# 4_SDCard.net
KiCad netlist of a schematic drawn in Altium Designer
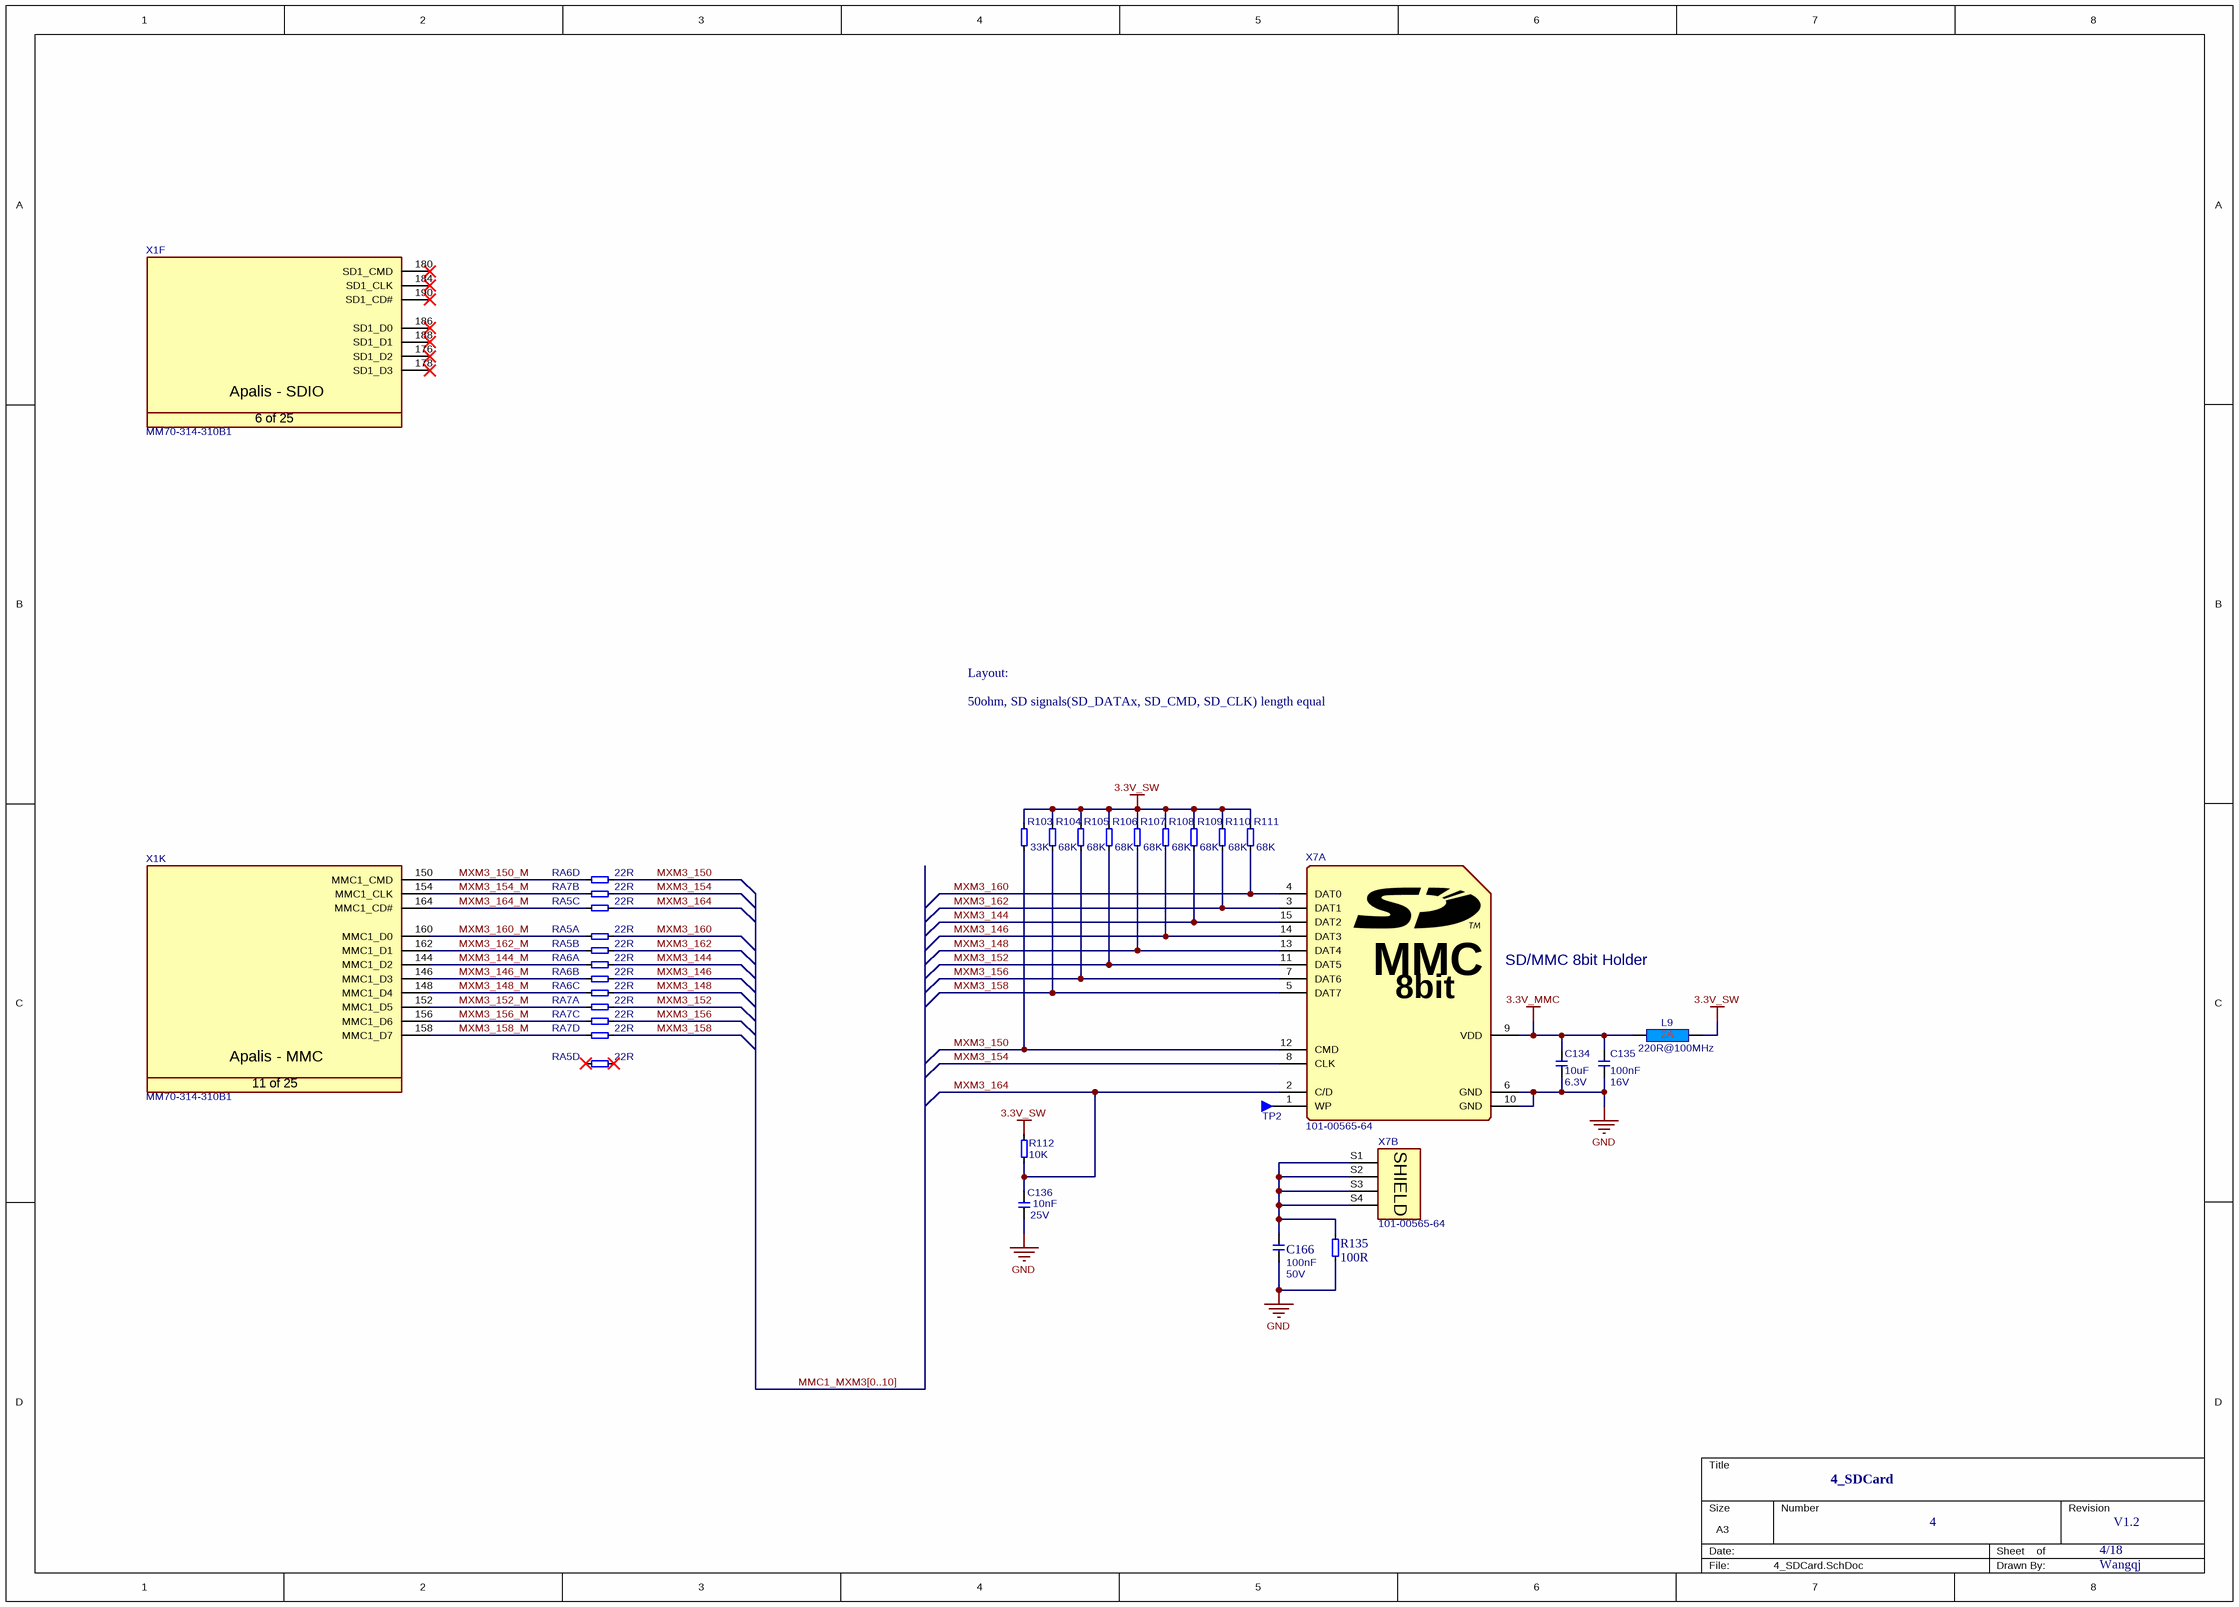
[diagram p0: 4_SDCard.SchDoc]

(export (version "E")
  (design (tool "Eeschema 10.0.6"))
  (components
    (comp (ref "C134")
      (value "10uF")
      (footprint "T_CAPC0603X33N")
      (description "Capacitor Ceramic X5R 10uF 6.3V 20% 0603")
      (fields (field (name "TOLERANCE") "20%") (field (name "RATING") "6.3V"))
      (libsource (lib "Apalis Evaluation Board") (part "C-X5R-10uF-6.3V-20%-0603"))
    )
    (comp (ref "C135")
      (value "100nF")
      (footprint "T_CAPC0603X33N")
      (description "Capacitor Ceramic X7R 100nF 16V 10% 0603")
      (fields (field (name "TOLERANCE") "10%") (field (name "RATING") "16V"))
      (libsource (lib "Apalis Evaluation Board") (part "C-X7R-100nF-16V-10%-0603"))
    )
    (comp (ref "C136")
      (value "10nF")
      (footprint "T_CAPC0603X33N")
      (description "Capacitor Ceramic X7R 10nF 25V 10% 0603")
      (fields (field (name "TOLERANCE") "10%") (field (name "RATING") "25V"))
      (libsource (lib "Apalis Evaluation Board") (part "C-X7R-10nF-25V-10%-0603"))
    )
    (comp (ref "C166")
      (value "100nF")
      (footprint "T_CAPC0603X33N")
      (description "Capacitor Ceramic X7R 100nF 50V 20% 0603")
      (fields (field (name "TOLERANCE") "20%") (field (name "RATING") "50V"))
      (libsource (lib "Apalis Evaluation Board") (part "C-100nF-50V-20%-0603-X7R"))
    )
    (comp (ref "L9")
      (value "220R@100MHz")
      (footprint "INDC1608X95N")
      (description "220R@100MHz 2A EMI FILTER")
      (fields (field (name "TOLERANCE") "25%"))
      (libsource (lib "Apalis Evaluation Board") (part "L-220R@100MHz-2A-25%-0603"))
    )
    (comp (ref "R103")
      (value "33K")
      (footprint "T_RESC0603X30N")
      (description "Resistor 33 Kohm 63mW 5% 0603")
      (fields (field (name "TOLERANCE") "5%"))
      (libsource (lib "Apalis Evaluation Board") (part "R-33KR-63mW-5%-0603"))
    )
    (comp (ref "R104")
      (value "68K")
      (footprint "T_RESC0603X30N")
      (description "Resistor 68 Kohm 63mW 5% 0603")
      (fields (field (name "TOLERANCE") "5%"))
      (libsource (lib "Apalis Evaluation Board") (part "R-68KR-63mW-5%-0603"))
    )
    (comp (ref "R105")
      (value "68K")
      (footprint "T_RESC0603X30N")
      (description "Resistor 68 Kohm 63mW 5% 0603")
      (fields (field (name "TOLERANCE") "5%"))
      (libsource (lib "Apalis Evaluation Board") (part "R-68KR-63mW-5%-0603"))
    )
    (comp (ref "R106")
      (value "68K")
      (footprint "T_RESC0603X30N")
      (description "Resistor 68 Kohm 63mW 5% 0603")
      (fields (field (name "TOLERANCE") "5%"))
      (libsource (lib "Apalis Evaluation Board") (part "R-68KR-63mW-5%-0603"))
    )
    (comp (ref "R107")
      (value "68K")
      (footprint "T_RESC0603X30N")
      (description "Resistor 68 Kohm 63mW 5% 0603")
      (fields (field (name "TOLERANCE") "5%"))
      (libsource (lib "Apalis Evaluation Board") (part "R-68KR-63mW-5%-0603"))
    )
    (comp (ref "R108")
      (value "68K")
      (footprint "T_RESC0603X30N")
      (description "Resistor 68 Kohm 63mW 5% 0603")
      (fields (field (name "TOLERANCE") "5%"))
      (libsource (lib "Apalis Evaluation Board") (part "R-68KR-63mW-5%-0603"))
    )
    (comp (ref "R109")
      (value "68K")
      (footprint "T_RESC0603X30N")
      (description "Resistor 68 Kohm 63mW 5% 0603")
      (fields (field (name "TOLERANCE") "5%"))
      (libsource (lib "Apalis Evaluation Board") (part "R-68KR-63mW-5%-0603"))
    )
    (comp (ref "R110")
      (value "68K")
      (footprint "T_RESC0603X30N")
      (description "Resistor 68 Kohm 63mW 5% 0603")
      (fields (field (name "TOLERANCE") "5%"))
      (libsource (lib "Apalis Evaluation Board") (part "R-68KR-63mW-5%-0603"))
    )
    (comp (ref "R111")
      (value "68K")
      (footprint "T_RESC0603X30N")
      (description "Resistor 68 Kohm 63mW 5% 0603")
      (fields (field (name "TOLERANCE") "5%"))
      (libsource (lib "Apalis Evaluation Board") (part "R-68KR-63mW-5%-0603"))
    )
    (comp (ref "R112")
      (value "10K")
      (footprint "T_RESC0603X30N")
      (description "Resistor 10 Kohm 63mW 5% 0603")
      (fields (field (name "TOLERANCE") "5%"))
      (libsource (lib "Apalis Evaluation Board") (part "R-10KR-63mW-5%-0603"))
    )
    (comp (ref "R135")
      (value "100R")
      (footprint "T_RESC0603X30N")
      (description "Resistor 120 ohm 63mW 5% 0603")
      (fields (field (name "TOLERANCE") "5%"))
      (libsource (lib "Apalis Evaluation Board") (part "R-120R-63mW-5%-0603"))
    )
    (comp (ref "RA5")
      (value "22R")
      (footprint "T_Resistor_Array_X4")
      (description "Resistor Array 22 R 63mW 5% 1206")
      (fields (field (name "TOLERANCE") "5%"))
      (libsource (lib "Apalis Evaluation Board") (part "RA-22R-63mW-5%-1206-div"))
    )
    (comp (ref "RA6")
      (value "22R")
      (footprint "T_Resistor_Array_X4")
      (description "Resistor Array 22 R 63mW 5% 1206")
      (fields (field (name "TOLERANCE") "5%"))
      (libsource (lib "Apalis Evaluation Board") (part "RA-22R-63mW-5%-1206-div"))
    )
    (comp (ref "RA7")
      (value "22R")
      (footprint "T_Resistor_Array_X4")
      (description "Resistor Array 22 R 63mW 5% 1206")
      (fields (field (name "TOLERANCE") "5%"))
      (libsource (lib "Apalis Evaluation Board") (part "RA-22R-63mW-5%-1206-div"))
    )
    (comp (ref "TP2")
      (value "Testpin")
      (footprint "T_TP-THT")
      (description "Testpin TH")
      (libsource (lib "Apalis Evaluation Board") (part "Testpin"))
    )
    (comp (ref "X1")
      (value "CON-JAE-MM70-314-310B1-314-0.5mm")
      (footprint "T_JAE_MM70-314-310B1")
      (description "MXM3 Connector")
      (fields (field (name "MANUFACTURER PART NO.") "MM70-314-310B1"))
      (libsource (lib "Apalis Evaluation Board") (part "CON-JAE-MM70-314-310B1-314-0.5mm"))
    )
    (comp (ref "X7")
      (value "101-00565-64")
      (footprint "T_ AMPHENOL_101-00565")
      (description "SD/MMC 8bit Card Holder")
      (fields (field (name "MANUFACTURER PART NO.") "101-00565-64"))
      (libsource (lib "Apalis Evaluation Board") (part "CON-Amphenol-101-00565-64"))
    )
  )
  (nets
    (net (code "13") (name "/MXM3_144") (class "Default")
      (node (ref "R109") (pin "1") (pinfunction "1_1") (pintype "passive"))
      (node (ref "RA6") (pin "5") (pinfunction "5_5") (pintype "passive"))
      (node (ref "X7") (pin "15") (pinfunction "DAT2_15") (pintype "passive"))
    )
    (net (code "14") (name "/MXM3_144_M") (class "Default")
      (node (ref "RA6") (pin "1") (pinfunction "1_1") (pintype "passive"))
      (node (ref "X1") (pin "144") (pinfunction "MMC1_D2_144") (pintype "passive"))
    )
    (net (code "15") (name "/MXM3_146") (class "Default")
      (node (ref "R108") (pin "1") (pinfunction "1_1") (pintype "passive"))
      (node (ref "RA6") (pin "6") (pinfunction "6_6") (pintype "passive"))
      (node (ref "X7") (pin "14") (pinfunction "DAT3_14") (pintype "passive"))
    )
    (net (code "16") (name "/MXM3_146_M") (class "Default")
      (node (ref "RA6") (pin "2") (pinfunction "2_2") (pintype "passive"))
      (node (ref "X1") (pin "146") (pinfunction "MMC1_D3_146") (pintype "passive"))
    )
    (net (code "17") (name "/MXM3_148") (class "Default")
      (node (ref "R107") (pin "1") (pinfunction "1_1") (pintype "passive"))
      (node (ref "RA6") (pin "7") (pinfunction "7_7") (pintype "passive"))
      (node (ref "X7") (pin "13") (pinfunction "DAT4_13") (pintype "passive"))
    )
    (net (code "18") (name "/MXM3_148_M") (class "Default")
      (node (ref "RA6") (pin "3") (pinfunction "3_3") (pintype "passive"))
      (node (ref "X1") (pin "148") (pinfunction "MMC1_D4_148") (pintype "passive"))
    )
    (net (code "19") (name "/MXM3_150") (class "Default")
      (node (ref "R103") (pin "1") (pinfunction "1_1") (pintype "passive"))
      (node (ref "RA6") (pin "8") (pinfunction "8_8") (pintype "passive"))
      (node (ref "X7") (pin "12") (pinfunction "CMD_12") (pintype "passive"))
    )
    (net (code "20") (name "/MXM3_150_M") (class "Default")
      (node (ref "RA6") (pin "4") (pinfunction "4_4") (pintype "passive"))
      (node (ref "X1") (pin "150") (pinfunction "MMC1_CMD_150") (pintype "passive"))
    )
    (net (code "21") (name "/MXM3_152") (class "Default")
      (node (ref "R106") (pin "1") (pinfunction "1_1") (pintype "passive"))
      (node (ref "RA7") (pin "5") (pinfunction "5_5") (pintype "passive"))
      (node (ref "X7") (pin "11") (pinfunction "DAT5_11") (pintype "passive"))
    )
    (net (code "22") (name "/MXM3_152_M") (class "Default")
      (node (ref "RA7") (pin "1") (pinfunction "1_1") (pintype "passive"))
      (node (ref "X1") (pin "152") (pinfunction "MMC1_D5_152") (pintype "passive"))
    )
    (net (code "23") (name "/MXM3_154") (class "Default")
      (node (ref "RA7") (pin "6") (pinfunction "6_6") (pintype "passive"))
      (node (ref "X7") (pin "8") (pinfunction "CLK_8") (pintype "passive"))
    )
    (net (code "24") (name "/MXM3_154_M") (class "Default")
      (node (ref "RA7") (pin "2") (pinfunction "2_2") (pintype "passive"))
      (node (ref "X1") (pin "154") (pinfunction "MMC1_CLK_154") (pintype "passive"))
    )
    (net (code "25") (name "/MXM3_156") (class "Default")
      (node (ref "R105") (pin "1") (pinfunction "1_1") (pintype "passive"))
      (node (ref "RA7") (pin "7") (pinfunction "7_7") (pintype "passive"))
      (node (ref "X7") (pin "7") (pinfunction "DAT6_7") (pintype "passive"))
    )
    (net (code "26") (name "/MXM3_156_M") (class "Default")
      (node (ref "RA7") (pin "3") (pinfunction "3_3") (pintype "passive"))
      (node (ref "X1") (pin "156") (pinfunction "MMC1_D6_156") (pintype "passive"))
    )
    (net (code "27") (name "/MXM3_158") (class "Default")
      (node (ref "R104") (pin "1") (pinfunction "1_1") (pintype "passive"))
      (node (ref "RA7") (pin "8") (pinfunction "8_8") (pintype "passive"))
      (node (ref "X7") (pin "5") (pinfunction "DAT7_5") (pintype "passive"))
    )
    (net (code "28") (name "/MXM3_158_M") (class "Default")
      (node (ref "RA7") (pin "4") (pinfunction "4_4") (pintype "passive"))
      (node (ref "X1") (pin "158") (pinfunction "MMC1_D7_158") (pintype "passive"))
    )
    (net (code "29") (name "/MXM3_160") (class "Default")
      (node (ref "R111") (pin "1") (pinfunction "1_1") (pintype "passive"))
      (node (ref "RA5") (pin "5") (pinfunction "5_5") (pintype "passive"))
      (node (ref "X7") (pin "4") (pinfunction "DAT0_4") (pintype "passive"))
    )
    (net (code "30") (name "/MXM3_160_M") (class "Default")
      (node (ref "RA5") (pin "1") (pinfunction "1_1") (pintype "passive"))
      (node (ref "X1") (pin "160") (pinfunction "MMC1_D0_160") (pintype "passive"))
    )
    (net (code "31") (name "/MXM3_162") (class "Default")
      (node (ref "R110") (pin "1") (pinfunction "1_1") (pintype "passive"))
      (node (ref "RA5") (pin "6") (pinfunction "6_6") (pintype "passive"))
      (node (ref "X7") (pin "3") (pinfunction "DAT1_3") (pintype "passive"))
    )
    (net (code "32") (name "/MXM3_162_M") (class "Default")
      (node (ref "RA5") (pin "2") (pinfunction "2_2") (pintype "passive"))
      (node (ref "X1") (pin "162") (pinfunction "MMC1_D1_162") (pintype "passive"))
    )
    (net (code "33") (name "/MXM3_164") (class "Default")
      (node (ref "C136") (pin "2") (pinfunction "2_2") (pintype "passive"))
      (node (ref "R112") (pin "1") (pinfunction "1_1") (pintype "passive"))
      (node (ref "RA5") (pin "7") (pinfunction "7_7") (pintype "passive"))
      (node (ref "X7") (pin "2") (pinfunction "C/D_2") (pintype "passive"))
    )
    (net (code "34") (name "/MXM3_164_M") (class "Default")
      (node (ref "RA5") (pin "3") (pinfunction "3_3") (pintype "passive"))
      (node (ref "X1") (pin "164") (pinfunction "MMC1_CD#_164") (pintype "passive"))
    )
    (net (code "35") (name "3.3V_MMC") (class "Default")
      (node (ref "C134") (pin "2") (pinfunction "2_2") (pintype "passive"))
      (node (ref "C135") (pin "2") (pinfunction "2_2") (pintype "passive"))
      (node (ref "L9") (pin "1") (pinfunction "1_1") (pintype "passive"))
      (node (ref "X7") (pin "9") (pinfunction "VDD_9") (pintype "passive"))
    )
    (net (code "36") (name "3.3V_SW") (class "Default")
      (node (ref "L9") (pin "2") (pinfunction "2_2") (pintype "passive"))
      (node (ref "R103") (pin "2") (pinfunction "2_2") (pintype "passive"))
      (node (ref "R104") (pin "2") (pinfunction "2_2") (pintype "passive"))
      (node (ref "R105") (pin "2") (pinfunction "2_2") (pintype "passive"))
      (node (ref "R106") (pin "2") (pinfunction "2_2") (pintype "passive"))
      (node (ref "R107") (pin "2") (pinfunction "2_2") (pintype "passive"))
      (node (ref "R108") (pin "2") (pinfunction "2_2") (pintype "passive"))
      (node (ref "R109") (pin "2") (pinfunction "2_2") (pintype "passive"))
      (node (ref "R110") (pin "2") (pinfunction "2_2") (pintype "passive"))
      (node (ref "R111") (pin "2") (pinfunction "2_2") (pintype "passive"))
      (node (ref "R112") (pin "2") (pinfunction "2_2") (pintype "passive"))
    )
    (net (code "37") (name "GND") (class "Default")
      (node (ref "C134") (pin "1") (pinfunction "1_1") (pintype "passive"))
      (node (ref "C135") (pin "1") (pinfunction "1_1") (pintype "passive"))
      (node (ref "C136") (pin "1") (pinfunction "1_1") (pintype "passive"))
      (node (ref "C166") (pin "1") (pinfunction "1_1") (pintype "passive"))
      (node (ref "R135") (pin "1") (pinfunction "1_1") (pintype "passive"))
      (node (ref "X7") (pin "10") (pinfunction "GND_10") (pintype "passive"))
      (node (ref "X7") (pin "6") (pinfunction "GND_6") (pintype "passive"))
    )
    (net (code "38") (name "Net-(C166-Pad2)") (class "Default")
      (node (ref "C166") (pin "2") (pinfunction "2_2") (pintype "passive"))
      (node (ref "R135") (pin "2") (pinfunction "2_2") (pintype "passive"))
      (node (ref "X7") (pin "S1") (pinfunction "S_S1") (pintype "passive"))
      (node (ref "X7") (pin "S2") (pinfunction "S_S2") (pintype "passive"))
      (node (ref "X7") (pin "S3") (pinfunction "S_S3") (pintype "passive"))
      (node (ref "X7") (pin "S4") (pinfunction "S_S4") (pintype "passive"))
    )
    (net (code "39") (name "Net-(X7A-WP)") (class "Default")
      (node (ref "TP2") (pin "1") (pinfunction "1_1") (pintype "passive"))
      (node (ref "X7") (pin "1") (pinfunction "WP_1") (pintype "passive"))
    )
    (net (code "40") (name "unconnected-(RA5-Pad4)") (class "Default")
      (node (ref "RA5") (pin "4") (pinfunction "4_4") (pintype "passive+no_connect"))
    )
    (net (code "41") (name "unconnected-(RA5-Pad8)") (class "Default")
      (node (ref "RA5") (pin "8") (pinfunction "8_8") (pintype "passive+no_connect"))
    )
    (net (code "42") (name "unconnected-(X1F-SD1_CD#-Pad190)") (class "Default")
      (node (ref "X1") (pin "190") (pinfunction "SD1_CD#_190") (pintype "passive+no_connect"))
    )
    (net (code "43") (name "unconnected-(X1F-SD1_CLK-Pad184)") (class "Default")
      (node (ref "X1") (pin "184") (pinfunction "SD1_CLK_184") (pintype "passive+no_connect"))
    )
    (net (code "44") (name "unconnected-(X1F-SD1_CMD-Pad180)") (class "Default")
      (node (ref "X1") (pin "180") (pinfunction "SD1_CMD_180") (pintype "passive+no_connect"))
    )
    (net (code "45") (name "unconnected-(X1F-SD1_D0-Pad186)") (class "Default")
      (node (ref "X1") (pin "186") (pinfunction "SD1_D0_186") (pintype "passive+no_connect"))
    )
    (net (code "46") (name "unconnected-(X1F-SD1_D1-Pad188)") (class "Default")
      (node (ref "X1") (pin "188") (pinfunction "SD1_D1_188") (pintype "passive+no_connect"))
    )
    (net (code "47") (name "unconnected-(X1F-SD1_D2-Pad176)") (class "Default")
      (node (ref "X1") (pin "176") (pinfunction "SD1_D2_176") (pintype "passive+no_connect"))
    )
    (net (code "48") (name "unconnected-(X1F-SD1_D3-Pad178)") (class "Default")
      (node (ref "X1") (pin "178") (pinfunction "SD1_D3_178") (pintype "passive+no_connect"))
    )
  )
)
